# PR9016.net
KiCad netlist of a schematic drawn in EAGLE
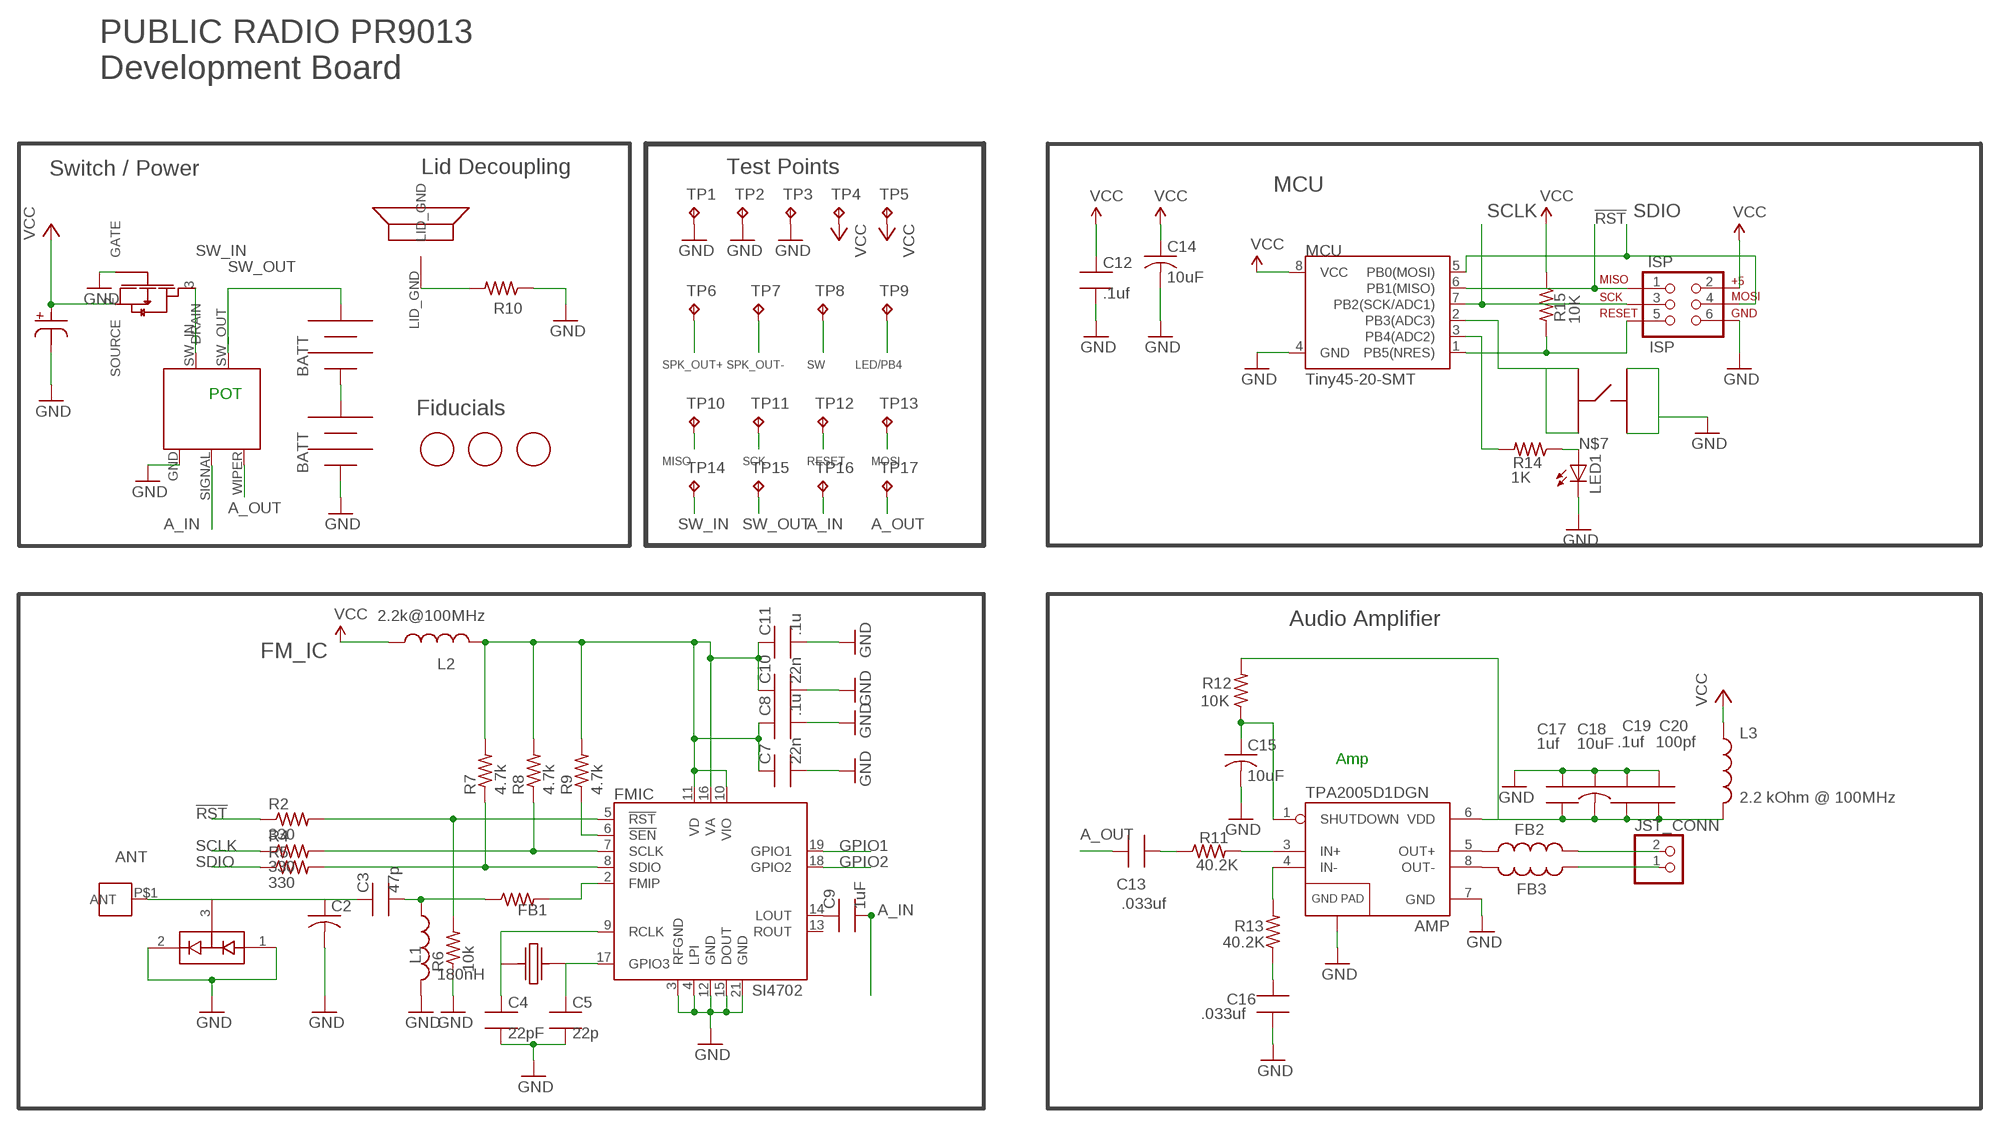
[diagram p0: schematic, sheet 1]

(export (version "E")
  (design (tool "Eeschema 10.0.6"))
  (components
    (comp (ref "AMP")
      (value "TPA2005D1DGN")
      (footprint "eagle-import:POWER-SOP8")
      (libsource (lib "eagle-import") (part "TPA2005D1DGN"))
    )
    (comp (ref "C1")
      (value "220uF")
      (footprint "eagle-import:NICHICON_SERIESUD")
      (libsource (lib "eagle-import") (part "NICHICON_SERIESUD"))
    )
    (comp (ref "C2")
      (value "C-USC0805")
      (footprint "eagle-import:C0805")
      (libsource (lib "eagle-import") (part "C-USC0805"))
    )
    (comp (ref "C3")
      (value "47p")
      (footprint "eagle-import:C0402_WORTHINGTON")
      (libsource (lib "eagle-import") (part "CAP_SMT"))
    )
    (comp (ref "C4")
      (value "22pF")
      (footprint "eagle-import:C0402_WORTHINGTON")
      (libsource (lib "eagle-import") (part "CAP_SMT"))
    )
    (comp (ref "C5")
      (value "22p")
      (footprint "eagle-import:C0402_WORTHINGTON")
      (libsource (lib "eagle-import") (part "CAP_SMT"))
    )
    (comp (ref "C7")
      (value "22n")
      (footprint "eagle-import:C0402_WORTHINGTON")
      (libsource (lib "eagle-import") (part "CAP_SMT"))
    )
    (comp (ref "C8")
      (value ".1u")
      (footprint "eagle-import:C0402_WORTHINGTON")
      (libsource (lib "eagle-import") (part "CAP_SMT"))
    )
    (comp (ref "C9")
      (value "1uF")
      (footprint "eagle-import:C0402_WORTHINGTON")
      (libsource (lib "eagle-import") (part "CAP_SMT"))
    )
    (comp (ref "C10")
      (value "22n")
      (footprint "eagle-import:C0402_WORTHINGTON")
      (libsource (lib "eagle-import") (part "CAP_SMT"))
    )
    (comp (ref "C11")
      (value ".1u")
      (footprint "eagle-import:C0402_WORTHINGTON")
      (libsource (lib "eagle-import") (part "CAP_SMT"))
    )
    (comp (ref "C12")
      (value ".1uf")
      (footprint "eagle-import:C0402_WORTHINGTON")
      (libsource (lib "eagle-import") (part "CAP_SMT"))
    )
    (comp (ref "C13")
      (value ".033uf")
      (footprint "eagle-import:C0402_WORTHINGTON")
      (libsource (lib "eagle-import") (part "CAP_SMT"))
    )
    (comp (ref "C14")
      (value "10uF")
      (footprint "eagle-import:C0603")
      (libsource (lib "eagle-import") (part "C-USC0603"))
    )
    (comp (ref "C15")
      (value "10uF")
      (footprint "eagle-import:C0603")
      (libsource (lib "eagle-import") (part "C-USC0603"))
    )
    (comp (ref "C16")
      (value ".033uf")
      (footprint "eagle-import:C0402_WORTHINGTON")
      (libsource (lib "eagle-import") (part "CAP_SMT"))
    )
    (comp (ref "C17")
      (value "1uf")
      (footprint "eagle-import:C0402_WORTHINGTON")
      (libsource (lib "eagle-import") (part "CAP_SMT"))
    )
    (comp (ref "C18")
      (value "10uF")
      (footprint "eagle-import:C0603")
      (libsource (lib "eagle-import") (part "C-USC0603"))
    )
    (comp (ref "C19")
      (value ".1uf")
      (footprint "eagle-import:C0402_WORTHINGTON")
      (libsource (lib "eagle-import") (part "CAP_SMT"))
    )
    (comp (ref "C20")
      (value "100pf")
      (footprint "eagle-import:C0402_WORTHINGTON")
      (libsource (lib "eagle-import") (part "CAP_SMT"))
    )
    (comp (ref "D1")
      (value "BAV99")
      (footprint "eagle-import:SOT23")
      (libsource (lib "eagle-import") (part "BAV99"))
    )
    (comp (ref "FB1")
      (value "R-US_R0402")
      (footprint "eagle-import:R0402")
      (libsource (lib "eagle-import") (part "R-US_R0402"))
    )
    (comp (ref "FB2")
      (value "INDUCTOR0805")
      (footprint "eagle-import:0805")
      (libsource (lib "eagle-import") (part "INDUCTOR0805"))
    )
    (comp (ref "FB3")
      (value "INDUCTOR0805")
      (footprint "eagle-import:0805")
      (libsource (lib "eagle-import") (part "INDUCTOR0805"))
    )
    (comp (ref "FET2")
      (value "AO3435")
      (footprint "eagle-import:AO3435")
      (libsource (lib "eagle-import") (part "AO3435"))
    )
    (comp (ref "FMIC")
      (value "SI4702")
      (footprint "eagle-import:SI470X")
      (libsource (lib "eagle-import") (part "SI470X"))
    )
    (comp (ref "ISP")
      (value "ISP")
      (footprint "eagle-import:2X3-NS")
      (libsource (lib "eagle-import") (part "AVR_SPI_PRG_6NS"))
    )
    (comp (ref "J1")
      (value "M3_SCREW_POST")
      (footprint "eagle-import:M3_SCREW_POST")
      (libsource (lib "eagle-import") (part "M3_SCREW_POST"))
    )
    (comp (ref "JP5")
      (value "BK-92_MPD_AA_BATT_CLIP")
      (footprint "eagle-import:BK-92_MPD_AA_BATT_CLIP")
      (libsource (lib "eagle-import") (part "BK-92_MPD_AA_BATT_CLIP"))
    )
    (comp (ref "JP6")
      (value "BK-92_MPD_AA_BATT_CLIP")
      (footprint "eagle-import:BK-92_MPD_AA_BATT_CLIP")
      (libsource (lib "eagle-import") (part "BK-92_MPD_AA_BATT_CLIP"))
    )
    (comp (ref "JST_CONN")
      (value "JST_2PIN-SMT-RA")
      (footprint "eagle-import:JST-PH-2-SMT-RA")
      (libsource (lib "eagle-import") (part "JST_2PIN-SMT-RA"))
    )
    (comp (ref "L1")
      (value "180nH")
      (footprint "eagle-import:0805")
      (libsource (lib "eagle-import") (part "INDUCTOR0805"))
    )
    (comp (ref "L2")
      (value "2.2k@100MHz")
      (footprint "eagle-import:C0402_WORTHINGTON")
      (libsource (lib "eagle-import") (part "INDUCTOR"))
    )
    (comp (ref "L3")
      (value "2.2 kOhm @ 100MHz")
      (footprint "eagle-import:C0402_WORTHINGTON")
      (libsource (lib "eagle-import") (part "INDUCTOR"))
    )
    (comp (ref "LED1")
      (value "LEDSML0603")
      (footprint "eagle-import:SML0603")
      (libsource (lib "eagle-import") (part "LEDSML0603"))
    )
    (comp (ref "MCU")
      (value "Tiny45-20-SMT")
      (footprint "eagle-import:SO08-EIAJ")
      (libsource (lib "eagle-import") (part "ATTINY45TINY85-20-SMT"))
    )
    (comp (ref "R1")
      (value "RV170SF_TAIWANA_POT_SW")
      (footprint "eagle-import:RV170SF_TAIWANA_POT_SW")
      (libsource (lib "eagle-import") (part "RV170SF_TAIWANA_POT_SW"))
    )
    (comp (ref "R2")
      (value "330")
      (footprint "eagle-import:C0402_WORTHINGTON")
      (libsource (lib "eagle-import") (part "RES_SMT"))
    )
    (comp (ref "R4")
      (value "330")
      (footprint "eagle-import:C0402_WORTHINGTON")
      (libsource (lib "eagle-import") (part "RES_SMT"))
    )
    (comp (ref "R5")
      (value "330")
      (footprint "eagle-import:C0402_WORTHINGTON")
      (libsource (lib "eagle-import") (part "RES_SMT"))
    )
    (comp (ref "R6")
      (value "10k")
      (footprint "eagle-import:R0402")
      (libsource (lib "eagle-import") (part "R-US_R0402"))
    )
    (comp (ref "R7")
      (value "4.7k")
      (footprint "eagle-import:C0402_WORTHINGTON")
      (libsource (lib "eagle-import") (part "RES_SMT"))
    )
    (comp (ref "R8")
      (value "4.7k")
      (footprint "eagle-import:C0402_WORTHINGTON")
      (libsource (lib "eagle-import") (part "RES_SMT"))
    )
    (comp (ref "R9")
      (value "4.7k")
      (footprint "eagle-import:C0402_WORTHINGTON")
      (libsource (lib "eagle-import") (part "RES_SMT"))
    )
    (comp (ref "R10")
      (value "R-US_R0805")
      (footprint "eagle-import:R0805")
      (libsource (lib "eagle-import") (part "R-US_R0805"))
    )
    (comp (ref "R11")
      (value "40.2K")
      (footprint "eagle-import:C0402_WORTHINGTON")
      (libsource (lib "eagle-import") (part "RES_SMT"))
    )
    (comp (ref "R12")
      (value "10K")
      (footprint "eagle-import:C0402_WORTHINGTON")
      (libsource (lib "eagle-import") (part "RES_SMT"))
    )
    (comp (ref "R13")
      (value "40.2K")
      (footprint "eagle-import:C0402_WORTHINGTON")
      (libsource (lib "eagle-import") (part "RES_SMT"))
    )
    (comp (ref "R14")
      (value "1K")
      (footprint "eagle-import:C0402_WORTHINGTON")
      (libsource (lib "eagle-import") (part "RES_SMT"))
    )
    (comp (ref "R15")
      (value "10K")
      (footprint "eagle-import:C0402_WORTHINGTON")
      (libsource (lib "eagle-import") (part "RES_SMT"))
    )
    (comp (ref "SW1")
      (value "C&K_PTS645")
      (footprint "eagle-import:C&K_TACTILE_SWITCH")
      (libsource (lib "eagle-import") (part "C&K_PTS645"))
    )
    (comp (ref "TP1")
      (value "TPTP20R")
      (footprint "eagle-import:TP20R")
      (libsource (lib "eagle-import") (part "TPTP20R"))
    )
    (comp (ref "TP2")
      (value "TPTP20R")
      (footprint "eagle-import:TP20R")
      (libsource (lib "eagle-import") (part "TPTP20R"))
    )
    (comp (ref "TP3")
      (value "TPTP20R")
      (footprint "eagle-import:TP20R")
      (libsource (lib "eagle-import") (part "TPTP20R"))
    )
    (comp (ref "TP4")
      (value "TPTP20R")
      (footprint "eagle-import:TP20R")
      (libsource (lib "eagle-import") (part "TPTP20R"))
    )
    (comp (ref "TP5")
      (value "TPTP20R")
      (footprint "eagle-import:TP20R")
      (libsource (lib "eagle-import") (part "TPTP20R"))
    )
    (comp (ref "TP6")
      (value "TPTP20R")
      (footprint "eagle-import:TP20R")
      (libsource (lib "eagle-import") (part "TPTP20R"))
    )
    (comp (ref "TP7")
      (value "TPTP20R")
      (footprint "eagle-import:TP20R")
      (libsource (lib "eagle-import") (part "TPTP20R"))
    )
    (comp (ref "TP8")
      (value "TPTP20R")
      (footprint "eagle-import:TP20R")
      (libsource (lib "eagle-import") (part "TPTP20R"))
    )
    (comp (ref "TP9")
      (value "TPTP20R")
      (footprint "eagle-import:TP20R")
      (libsource (lib "eagle-import") (part "TPTP20R"))
    )
    (comp (ref "TP10")
      (value "TPTP20R")
      (footprint "eagle-import:TP20R")
      (libsource (lib "eagle-import") (part "TPTP20R"))
    )
    (comp (ref "TP11")
      (value "TPTP20R")
      (footprint "eagle-import:TP20R")
      (libsource (lib "eagle-import") (part "TPTP20R"))
    )
    (comp (ref "TP12")
      (value "TPTP20R")
      (footprint "eagle-import:TP20R")
      (libsource (lib "eagle-import") (part "TPTP20R"))
    )
    (comp (ref "TP13")
      (value "TPTP20R")
      (footprint "eagle-import:TP20R")
      (libsource (lib "eagle-import") (part "TPTP20R"))
    )
    (comp (ref "TP14")
      (value "TPTP20R")
      (footprint "eagle-import:TP20R")
      (libsource (lib "eagle-import") (part "TPTP20R"))
    )
    (comp (ref "TP15")
      (value "TPTP20R")
      (footprint "eagle-import:TP20R")
      (libsource (lib "eagle-import") (part "TPTP20R"))
    )
    (comp (ref "TP16")
      (value "TPTP20R")
      (footprint "eagle-import:TP20R")
      (libsource (lib "eagle-import") (part "TPTP20R"))
    )
    (comp (ref "TP17")
      (value "TPTP20R")
      (footprint "eagle-import:TP20R")
      (libsource (lib "eagle-import") (part "TPTP20R"))
    )
    (comp (ref "U$1")
      (value "CE32A_FOR_JST")
      (footprint "eagle-import:CE32A_FOR_JST")
      (libsource (lib "eagle-import") (part "PR_Parts_Library_CE32A_FOR_JST"))
    )
    (comp (ref "U$3")
      (value "FIDUCIAL")
      (footprint "eagle-import:FIDUCIAL_1MM")
      (libsource (lib "eagle-import") (part "FIDUCIAL"))
    )
    (comp (ref "U$4")
      (value "FIDUCIAL")
      (footprint "eagle-import:FIDUCIAL_1MM")
      (libsource (lib "eagle-import") (part "FIDUCIAL"))
    )
    (comp (ref "U$5")
      (value "FIDUCIAL")
      (footprint "eagle-import:FIDUCIAL_1MM")
      (libsource (lib "eagle-import") (part "FIDUCIAL"))
    )
    (comp (ref "U$6")
      (value "ABS25XTAL")
      (footprint "eagle-import:ABS25XTAL")
      (libsource (lib "eagle-import") (part "ABS25XTAL"))
    )
  )
  (nets
    (net (code "1") (name "/ANT") (class "Default")
      (node (ref "C2") (pin "1") (pinfunction "1_1") (pintype "passive"))
      (node (ref "C3") (pin "1") (pinfunction "1_1") (pintype "passive"))
      (node (ref "D1") (pin "3") (pinfunction "COM_3") (pintype "bidirectional"))
      (node (ref "J1") (pin "P$1") (pinfunction "ANT_P$1") (pintype "bidirectional"))
    )
    (net (code "2") (name "/A_IN") (class "Default")
      (node (ref "C9") (pin "2") (pinfunction "2_2") (pintype "passive"))
      (node (ref "R1") (pin "SIGNAL") (pinfunction "SIGNAL_SIGNAL") (pintype "bidirectional"))
      (node (ref "TP16") (pin "TP") (pinfunction "TP_TP") (pintype "input"))
    )
    (net (code "3") (name "/A_OUT") (class "Default")
      (node (ref "C13") (pin "1") (pinfunction "1_1") (pintype "passive"))
      (node (ref "R1") (pin "WIPER") (pinfunction "WIPER_WIPER") (pintype "bidirectional"))
      (node (ref "TP17") (pin "TP") (pinfunction "TP_TP") (pintype "input"))
    )
    (net (code "4") (name "/GPIO1") (class "Default")
      (node (ref "FMIC") (pin "19") (pinfunction "GPIO1_19") (pintype "bidirectional"))
    )
    (net (code "5") (name "/GPIO2") (class "Default")
      (node (ref "FMIC") (pin "18") (pinfunction "GPIO2_18") (pintype "bidirectional"))
    )
    (net (code "6") (name "/LED{slash}PB4") (class "Default")
      (node (ref "MCU") (pin "3") (pinfunction "PB4(ADC2)_3") (pintype "bidirectional"))
      (node (ref "R14") (pin "2") (pinfunction "2_2") (pintype "passive"))
      (node (ref "TP9") (pin "TP") (pinfunction "TP_TP") (pintype "input"))
    )
    (net (code "7") (name "/N$7") (class "Default")
      (node (ref "LED1") (pin "A") (pinfunction "A_A") (pintype "passive"))
      (node (ref "R14") (pin "1") (pinfunction "1_1") (pintype "passive"))
    )
    (net (code "8") (name "/RESET") (class "Default")
      (node (ref "ISP") (pin "5") (pinfunction "5_5") (pintype "passive"))
      (node (ref "MCU") (pin "1") (pinfunction "PB5(NRES)_1") (pintype "bidirectional"))
      (node (ref "R15") (pin "2") (pinfunction "2_2") (pintype "passive"))
      (node (ref "TP12") (pin "TP") (pinfunction "TP_TP") (pintype "input"))
    )
    (net (code "9") (name "/SCLK") (class "Default")
      (node (ref "ISP") (pin "3") (pinfunction "3_3") (pintype "passive"))
      (node (ref "MCU") (pin "7") (pinfunction "PB2(SCK/ADC1)_7") (pintype "bidirectional"))
      (node (ref "R4") (pin "1") (pinfunction "1_1") (pintype "passive"))
      (node (ref "TP11") (pin "TP") (pinfunction "TP_TP") (pintype "input"))
    )
    (net (code "10") (name "/SDIO") (class "Default")
      (node (ref "ISP") (pin "4") (pinfunction "4_4") (pintype "passive"))
      (node (ref "MCU") (pin "5") (pinfunction "PB0(MOSI)_5") (pintype "bidirectional"))
      (node (ref "R5") (pin "1") (pinfunction "1_1") (pintype "passive"))
      (node (ref "TP13") (pin "TP") (pinfunction "TP_TP") (pintype "input"))
    )
    (net (code "11") (name "/SPK_OUT+") (class "Default")
      (node (ref "FB2") (pin "2") (pinfunction "2_2") (pintype "passive"))
      (node (ref "JST_CONN") (pin "2") (pinfunction "1_2") (pintype "passive"))
      (node (ref "TP6") (pin "TP") (pinfunction "TP_TP") (pintype "input"))
    )
    (net (code "12") (name "/SPK_OUT-") (class "Default")
      (node (ref "FB3") (pin "1") (pinfunction "1_1") (pintype "passive"))
      (node (ref "JST_CONN") (pin "1") (pinfunction "2_1") (pintype "passive"))
      (node (ref "TP7") (pin "TP") (pinfunction "TP_TP") (pintype "input"))
    )
    (net (code "13") (name "/SW") (class "Default")
      (node (ref "MCU") (pin "2") (pinfunction "PB3(ADC3)_2") (pintype "bidirectional"))
      (node (ref "SW1") (pin "P$3") (pinfunction "P$3_P$3") (pintype "bidirectional"))
      (node (ref "SW1") (pin "P$4") (pinfunction "P$4_P$4") (pintype "bidirectional"))
      (node (ref "TP8") (pin "TP") (pinfunction "TP_TP") (pintype "input"))
    )
    (net (code "14") (name "/SW_IN") (class "Default")
      (node (ref "FET2") (pin "3") (pinfunction "DRAIN_3") (pintype "bidirectional"))
      (node (ref "R1") (pin "SW_IN") (pinfunction "SW_IN_SW_IN") (pintype "bidirectional"))
      (node (ref "TP14") (pin "TP") (pinfunction "TP_TP") (pintype "input"))
    )
    (net (code "15") (name "/SW_OUT") (class "Default")
      (node (ref "JP5") (pin "POS") (pinfunction "POS_POS") (pintype "bidirectional"))
      (node (ref "JP5") (pin "POS@2") (pinfunction "POS_POS@2") (pintype "bidirectional"))
      (node (ref "R1") (pin "SW_OUT") (pinfunction "SW_OUT_SW_OUT") (pintype "bidirectional"))
      (node (ref "TP15") (pin "TP") (pinfunction "TP_TP") (pintype "input"))
    )
    (net (code "16") (name "/~{RST}") (class "Default")
      (node (ref "ISP") (pin "1") (pinfunction "1_1") (pintype "passive"))
      (node (ref "MCU") (pin "6") (pinfunction "PB1(MISO)_6") (pintype "bidirectional"))
      (node (ref "R2") (pin "1") (pinfunction "1_1") (pintype "passive"))
      (node (ref "TP10") (pin "TP") (pinfunction "TP_TP") (pintype "input"))
    )
    (net (code "17") (name "GND") (class "Default")
      (node (ref "AMP") (pin "7") (pinfunction "GND_7") (pintype "power_in"))
      (node (ref "AMP") (pin "9") (pinfunction "GND_9") (pintype "power_in"))
      (node (ref "C1") (pin "P$2") (pinfunction "P$2_P$2") (pintype "bidirectional"))
      (node (ref "C10") (pin "2") (pinfunction "2_2") (pintype "passive"))
      (node (ref "C11") (pin "2") (pinfunction "2_2") (pintype "passive"))
      (node (ref "C12") (pin "2") (pinfunction "2_2") (pintype "passive"))
      (node (ref "C14") (pin "2") (pinfunction "2_2") (pintype "passive"))
      (node (ref "C15") (pin "2") (pinfunction "2_2") (pintype "passive"))
      (node (ref "C16") (pin "1") (pinfunction "1_1") (pintype "passive"))
      (node (ref "C17") (pin "1") (pinfunction "1_1") (pintype "passive"))
      (node (ref "C18") (pin "1") (pinfunction "1_1") (pintype "passive"))
      (node (ref "C19") (pin "1") (pinfunction "1_1") (pintype "passive"))
      (node (ref "C2") (pin "2") (pinfunction "2_2") (pintype "passive"))
      (node (ref "C20") (pin "1") (pinfunction "1_1") (pintype "passive"))
      (node (ref "C4") (pin "2") (pinfunction "2_2") (pintype "passive"))
      (node (ref "C5") (pin "2") (pinfunction "2_2") (pintype "passive"))
      (node (ref "C7") (pin "2") (pinfunction "2_2") (pintype "passive"))
      (node (ref "C8") (pin "2") (pinfunction "2_2") (pintype "passive"))
      (node (ref "D1") (pin "1") (pinfunction "A1_1") (pintype "bidirectional"))
      (node (ref "D1") (pin "2") (pinfunction "C2_2") (pintype "bidirectional"))
      (node (ref "FET2") (pin "1") (pinfunction "GATE_1") (pintype "bidirectional"))
      (node (ref "FMIC") (pin "12") (pinfunction "GND_12") (pintype "bidirectional"))
      (node (ref "FMIC") (pin "15") (pinfunction "DOUT_15") (pintype "bidirectional"))
      (node (ref "FMIC") (pin "21") (pinfunction "GND_21") (pintype "bidirectional"))
      (node (ref "FMIC") (pin "3") (pinfunction "RFGND_3") (pintype "bidirectional"))
      (node (ref "FMIC") (pin "4") (pinfunction "LPI_4") (pintype "bidirectional"))
      (node (ref "ISP") (pin "6") (pinfunction "6_6") (pintype "passive"))
      (node (ref "JP6") (pin "NEG") (pinfunction "NEG_NEG") (pintype "bidirectional"))
      (node (ref "JP6") (pin "NEG@2") (pinfunction "NEG_NEG@2") (pintype "bidirectional"))
      (node (ref "L1") (pin "2") (pinfunction "2_2") (pintype "passive"))
      (node (ref "LED1") (pin "C") (pinfunction "C_C") (pintype "passive"))
      (node (ref "MCU") (pin "4") (pinfunction "GND_4") (pintype "bidirectional"))
      (node (ref "R1") (pin "GND") (pinfunction "GND_GND") (pintype "bidirectional"))
      (node (ref "R10") (pin "1") (pinfunction "1_1") (pintype "passive"))
      (node (ref "R6") (pin "1") (pinfunction "1_1") (pintype "passive"))
      (node (ref "SW1") (pin "P$1") (pinfunction "P$1_P$1") (pintype "bidirectional"))
      (node (ref "SW1") (pin "P$2") (pinfunction "P$2_P$2") (pintype "bidirectional"))
      (node (ref "TP1") (pin "TP") (pinfunction "TP_TP") (pintype "input"))
      (node (ref "TP2") (pin "TP") (pinfunction "TP_TP") (pintype "input"))
      (node (ref "TP3") (pin "TP") (pinfunction "TP_TP") (pintype "input"))
    )
    (net (code "18") (name "Net-(AMP-IN+)") (class "Default")
      (node (ref "AMP") (pin "3") (pinfunction "IN+_3") (pintype "bidirectional"))
      (node (ref "R11") (pin "2") (pinfunction "2_2") (pintype "passive"))
    )
    (net (code "19") (name "Net-(AMP-IN-)") (class "Default")
      (node (ref "AMP") (pin "4") (pinfunction "IN-_4") (pintype "bidirectional"))
      (node (ref "R13") (pin "2") (pinfunction "2_2") (pintype "passive"))
    )
    (net (code "20") (name "Net-(AMP-OUT+)") (class "Default")
      (node (ref "AMP") (pin "5") (pinfunction "OUT+_5") (pintype "bidirectional"))
      (node (ref "FB2") (pin "1") (pinfunction "1_1") (pintype "passive"))
    )
    (net (code "21") (name "Net-(AMP-OUT-)") (class "Default")
      (node (ref "AMP") (pin "8") (pinfunction "OUT-_8") (pintype "bidirectional"))
      (node (ref "FB3") (pin "2") (pinfunction "2_2") (pintype "passive"))
    )
    (net (code "22") (name "Net-(AMP-SHUTDOWN)") (class "Default")
      (node (ref "AMP") (pin "1") (pinfunction "SHUTDOWN_1") (pintype "input"))
      (node (ref "C15") (pin "1") (pinfunction "1_1") (pintype "passive"))
      (node (ref "R12") (pin "1") (pinfunction "1_1") (pintype "passive"))
    )
    (net (code "23") (name "Net-(AMP-VDD)") (class "Default")
      (node (ref "AMP") (pin "6") (pinfunction "VDD_6") (pintype "power_in"))
      (node (ref "C17") (pin "2") (pinfunction "2_2") (pintype "passive"))
      (node (ref "C18") (pin "2") (pinfunction "2_2") (pintype "passive"))
      (node (ref "C19") (pin "2") (pinfunction "2_2") (pintype "passive"))
      (node (ref "C20") (pin "2") (pinfunction "2_2") (pintype "passive"))
      (node (ref "L3") (pin "2") (pinfunction "2_2") (pintype "passive"))
      (node (ref "R12") (pin "2") (pinfunction "2_2") (pintype "passive"))
    )
    (net (code "24") (name "Net-(C3-Pad2)") (class "Default")
      (node (ref "C3") (pin "2") (pinfunction "2_2") (pintype "passive"))
      (node (ref "FB1") (pin "1") (pinfunction "1_1") (pintype "passive"))
      (node (ref "L1") (pin "1") (pinfunction "1_1") (pintype "passive"))
    )
    (net (code "25") (name "Net-(C13-Pad2)") (class "Default")
      (node (ref "C13") (pin "2") (pinfunction "2_2") (pintype "passive"))
      (node (ref "R11") (pin "1") (pinfunction "1_1") (pintype "passive"))
    )
    (net (code "26") (name "Net-(C16-Pad2)") (class "Default")
      (node (ref "C16") (pin "2") (pinfunction "2_2") (pintype "passive"))
      (node (ref "R13") (pin "1") (pinfunction "1_1") (pintype "passive"))
    )
    (net (code "27") (name "Net-(FMIC-FMIP)") (class "Default")
      (node (ref "FB1") (pin "2") (pinfunction "2_2") (pintype "passive"))
      (node (ref "FMIC") (pin "2") (pinfunction "FMIP_2") (pintype "bidirectional"))
    )
    (net (code "28") (name "Net-(FMIC-GPIO3)") (class "Default")
      (node (ref "C5") (pin "1") (pinfunction "1_1") (pintype "passive"))
      (node (ref "FMIC") (pin "17") (pinfunction "GPIO3_17") (pintype "bidirectional"))
      (node (ref "U$6") (pin "P$4") (pinfunction "P$4_P$4") (pintype "bidirectional"))
    )
    (net (code "29") (name "Net-(FMIC-LOUT)") (class "Default")
      (node (ref "C9") (pin "1") (pinfunction "1_1") (pintype "passive"))
      (node (ref "FMIC") (pin "14") (pinfunction "LOUT_14") (pintype "bidirectional"))
    )
    (net (code "30") (name "Net-(FMIC-RCLK)") (class "Default")
      (node (ref "C4") (pin "1") (pinfunction "1_1") (pintype "passive"))
      (node (ref "FMIC") (pin "9") (pinfunction "RCLK_9") (pintype "bidirectional"))
      (node (ref "U$6") (pin "P$1") (pinfunction "P$1_P$1") (pintype "bidirectional"))
    )
    (net (code "31") (name "Net-(FMIC-SCLK)") (class "Default")
      (node (ref "FMIC") (pin "7") (pinfunction "SCLK_7") (pintype "bidirectional"))
      (node (ref "R4") (pin "2") (pinfunction "2_2") (pintype "passive"))
      (node (ref "R8") (pin "1") (pinfunction "1_1") (pintype "passive"))
    )
    (net (code "32") (name "Net-(FMIC-SDIO)") (class "Default")
      (node (ref "FMIC") (pin "8") (pinfunction "SDIO_8") (pintype "bidirectional"))
      (node (ref "R5") (pin "2") (pinfunction "2_2") (pintype "passive"))
      (node (ref "R7") (pin "1") (pinfunction "1_1") (pintype "passive"))
    )
    (net (code "33") (name "Net-(FMIC-VA)") (class "Default")
      (node (ref "C10") (pin "1") (pinfunction "1_1") (pintype "passive"))
      (node (ref "C11") (pin "1") (pinfunction "1_1") (pintype "passive"))
      (node (ref "C7") (pin "1") (pinfunction "1_1") (pintype "passive"))
      (node (ref "C8") (pin "1") (pinfunction "1_1") (pintype "passive"))
      (node (ref "FMIC") (pin "10") (pinfunction "VIO_10") (pintype "bidirectional"))
      (node (ref "FMIC") (pin "11") (pinfunction "VD_11") (pintype "bidirectional"))
      (node (ref "FMIC") (pin "16") (pinfunction "VA_16") (pintype "bidirectional"))
      (node (ref "L2") (pin "2") (pinfunction "2_2") (pintype "passive"))
      (node (ref "R7") (pin "2") (pinfunction "2_2") (pintype "passive"))
      (node (ref "R8") (pin "2") (pinfunction "2_2") (pintype "passive"))
      (node (ref "R9") (pin "2") (pinfunction "2_2") (pintype "passive"))
    )
    (net (code "34") (name "Net-(FMIC-~{RST})") (class "Default")
      (node (ref "FMIC") (pin "5") (pinfunction "~{RST}_5") (pintype "bidirectional"))
      (node (ref "R2") (pin "2") (pinfunction "2_2") (pintype "passive"))
      (node (ref "R6") (pin "2") (pinfunction "2_2") (pintype "passive"))
    )
    (net (code "35") (name "Net-(FMIC-~{SEN})") (class "Default")
      (node (ref "FMIC") (pin "6") (pinfunction "~{SEN}_6") (pintype "bidirectional"))
      (node (ref "R9") (pin "1") (pinfunction "1_1") (pintype "passive"))
    )
    (net (code "36") (name "Net-(JP5-NEG-PadNEG@2)") (class "Default")
      (node (ref "JP5") (pin "NEG") (pinfunction "NEG_NEG") (pintype "bidirectional"))
      (node (ref "JP5") (pin "NEG@2") (pinfunction "NEG_NEG@2") (pintype "bidirectional"))
      (node (ref "JP6") (pin "POS") (pinfunction "POS_POS") (pintype "bidirectional"))
      (node (ref "JP6") (pin "POS@2") (pinfunction "POS_POS@2") (pintype "bidirectional"))
    )
    (net (code "37") (name "Net-(R10-Pad2)") (class "Default")
      (node (ref "R10") (pin "2") (pinfunction "2_2") (pintype "passive"))
      (node (ref "U$1") (pin "LID_GND") (pinfunction "LID_GND_LID_GND") (pintype "bidirectional"))
    )
    (net (code "38") (name "VCC") (class "Default")
      (node (ref "C1") (pin "P$1") (pinfunction "P$1_P$1") (pintype "bidirectional"))
      (node (ref "C12") (pin "1") (pinfunction "1_1") (pintype "passive"))
      (node (ref "C14") (pin "1") (pinfunction "1_1") (pintype "passive"))
      (node (ref "FET2") (pin "2") (pinfunction "SOURCE_2") (pintype "bidirectional"))
      (node (ref "ISP") (pin "2") (pinfunction "2_2") (pintype "passive"))
      (node (ref "L2") (pin "1") (pinfunction "1_1") (pintype "passive"))
      (node (ref "L3") (pin "1") (pinfunction "1_1") (pintype "passive"))
      (node (ref "MCU") (pin "8") (pinfunction "VCC_8") (pintype "bidirectional"))
      (node (ref "R15") (pin "1") (pinfunction "1_1") (pintype "passive"))
      (node (ref "TP4") (pin "TP") (pinfunction "TP_TP") (pintype "input"))
      (node (ref "TP5") (pin "TP") (pinfunction "TP_TP") (pintype "input"))
    )
    (net (code "39") (name "unconnected-(FMIC-ROUT-Pad13)") (class "Default")
      (node (ref "FMIC") (pin "13") (pinfunction "ROUT_13") (pintype "bidirectional"))
    )
  )
)
